# tally-controller-shield.net
KiCad netlist of a schematic drawn in EAGLE
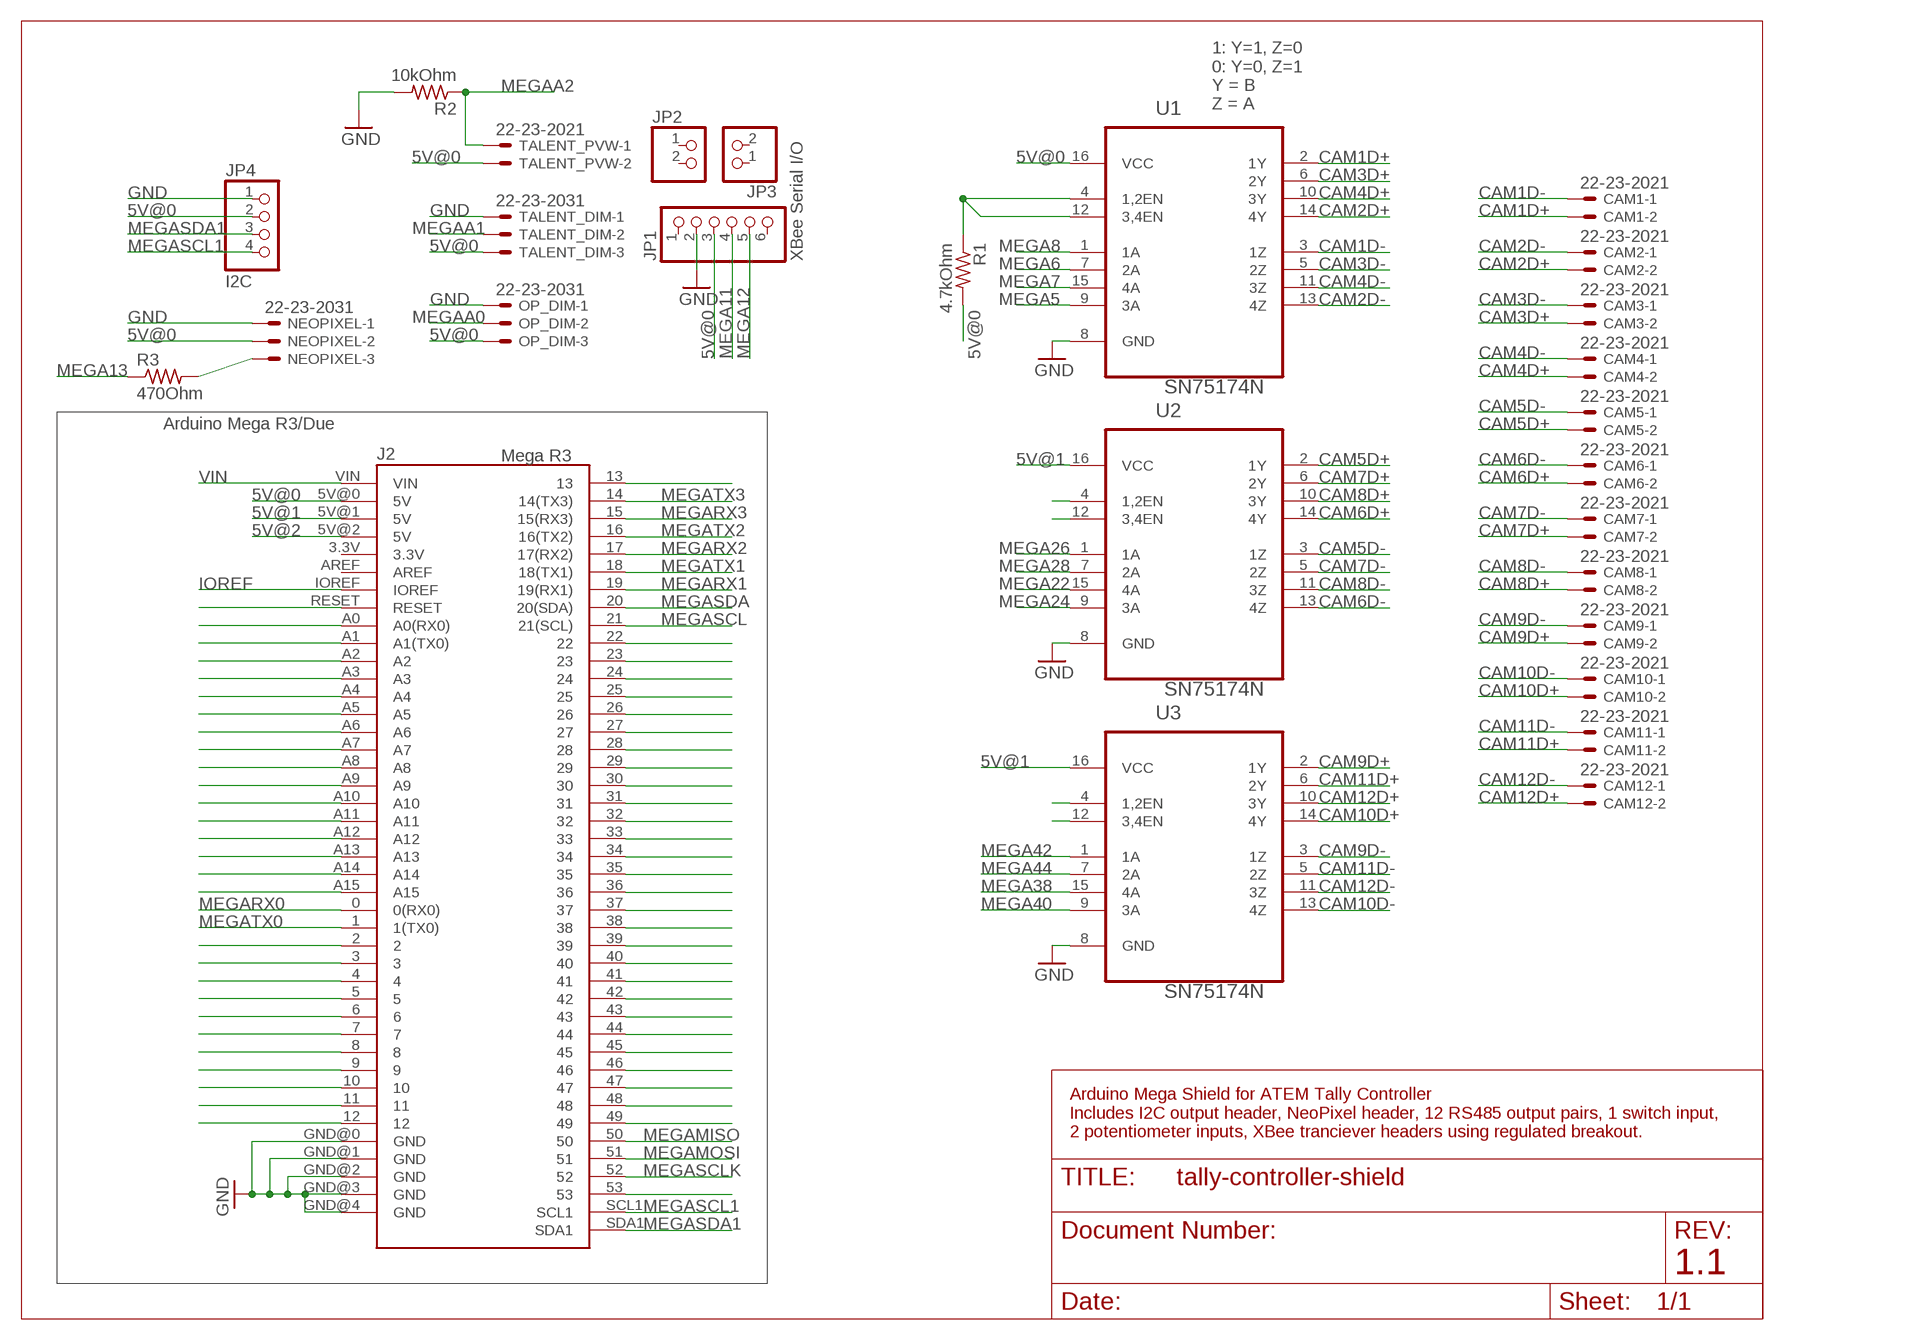
[diagram p0: schematic, sheet 1]

(export (version "E")
  (design (tool "Eeschema 10.0.6"))
  (components
    (comp (ref "CAM1")
      (value "22-23-2021")
      (footprint "eagle-import:22-23-2021")
      (fields (field (name "MF") "MOLEX"))
      (libsource (lib "eagle-import") (part "22-23-2021"))
    )
    (comp (ref "CAM2")
      (value "22-23-2021")
      (footprint "eagle-import:22-23-2021")
      (fields (field (name "MF") "MOLEX"))
      (libsource (lib "eagle-import") (part "22-23-2021"))
    )
    (comp (ref "CAM3")
      (value "22-23-2021")
      (footprint "eagle-import:22-23-2021")
      (fields (field (name "MF") "MOLEX"))
      (libsource (lib "eagle-import") (part "22-23-2021"))
    )
    (comp (ref "CAM4")
      (value "22-23-2021")
      (footprint "eagle-import:22-23-2021")
      (fields (field (name "MF") "MOLEX"))
      (libsource (lib "eagle-import") (part "22-23-2021"))
    )
    (comp (ref "CAM5")
      (value "22-23-2021")
      (footprint "eagle-import:22-23-2021")
      (fields (field (name "MF") "MOLEX"))
      (libsource (lib "eagle-import") (part "22-23-2021"))
    )
    (comp (ref "CAM6")
      (value "22-23-2021")
      (footprint "eagle-import:22-23-2021")
      (fields (field (name "MF") "MOLEX"))
      (libsource (lib "eagle-import") (part "22-23-2021"))
    )
    (comp (ref "CAM7")
      (value "22-23-2021")
      (footprint "eagle-import:22-23-2021")
      (fields (field (name "MF") "MOLEX"))
      (libsource (lib "eagle-import") (part "22-23-2021"))
    )
    (comp (ref "CAM8")
      (value "22-23-2021")
      (footprint "eagle-import:22-23-2021")
      (fields (field (name "MF") "MOLEX"))
      (libsource (lib "eagle-import") (part "22-23-2021"))
    )
    (comp (ref "CAM9")
      (value "22-23-2021")
      (footprint "eagle-import:22-23-2021")
      (fields (field (name "MF") "MOLEX"))
      (libsource (lib "eagle-import") (part "22-23-2021"))
    )
    (comp (ref "CAM10")
      (value "22-23-2021")
      (footprint "eagle-import:22-23-2021")
      (fields (field (name "MF") "MOLEX"))
      (libsource (lib "eagle-import") (part "22-23-2021"))
    )
    (comp (ref "CAM11")
      (value "22-23-2021")
      (footprint "eagle-import:22-23-2021")
      (fields (field (name "MF") "MOLEX"))
      (libsource (lib "eagle-import") (part "22-23-2021"))
    )
    (comp (ref "CAM12")
      (value "22-23-2021")
      (footprint "eagle-import:22-23-2021")
      (fields (field (name "MF") "MOLEX"))
      (libsource (lib "eagle-import") (part "22-23-2021"))
    )
    (comp (ref "J2")
      (value "Mega R3")
      (footprint "eagle-import:ARDUINO_MEGA")
      (libsource (lib "eagle-import") (part "ARDUINO-MEGAFULL"))
    )
    (comp (ref "JP1")
      (value "XBee Serial I/O")
      (footprint "eagle-import:1X06")
      (libsource (lib "eagle-import") (part "PINHD-1X6"))
    )
    (comp (ref "JP2")
      (value "PINHD-1X2")
      (footprint "eagle-import:1X02")
      (libsource (lib "eagle-import") (part "PINHD-1X2"))
    )
    (comp (ref "JP3")
      (value "PINHD-1X2")
      (footprint "eagle-import:1X02")
      (libsource (lib "eagle-import") (part "PINHD-1X2"))
    )
    (comp (ref "JP4")
      (value "I2C")
      (footprint "eagle-import:1X04")
      (libsource (lib "eagle-import") (part "PINHD-1X4"))
    )
    (comp (ref "NEOPIXEL")
      (value "22-23-2031")
      (footprint "eagle-import:22-23-2031")
      (fields (field (name "MF") "MOLEX"))
      (libsource (lib "eagle-import") (part "22-23-2031"))
    )
    (comp (ref "OP_DIM")
      (value "22-23-2031")
      (footprint "eagle-import:22-23-2031")
      (fields (field (name "MF") "MOLEX"))
      (libsource (lib "eagle-import") (part "22-23-2031"))
    )
    (comp (ref "R1")
      (value "4.7kOhm")
      (footprint "eagle-import:0207_10")
      (libsource (lib "eagle-import") (part "R-US_0207/10"))
    )
    (comp (ref "R2")
      (value "10kOhm")
      (footprint "eagle-import:0207_10")
      (libsource (lib "eagle-import") (part "R-US_0207/10"))
    )
    (comp (ref "R3")
      (value "470Ohm")
      (footprint "eagle-import:0207_10")
      (libsource (lib "eagle-import") (part "R-US_0207/10"))
    )
    (comp (ref "TALENT_DIM")
      (value "22-23-2031")
      (footprint "eagle-import:22-23-2031")
      (fields (field (name "MF") "MOLEX"))
      (libsource (lib "eagle-import") (part "22-23-2031"))
    )
    (comp (ref "TALENT_PVW")
      (value "22-23-2021")
      (footprint "eagle-import:22-23-2021")
      (fields (field (name "MF") "MOLEX"))
      (libsource (lib "eagle-import") (part "22-23-2021"))
    )
    (comp (ref "U1")
      (value "SN75174N")
      (footprint "eagle-import:DIP254P762X508-16")
      (fields (field (name "MF") "Texas Instruments"))
      (libsource (lib "eagle-import") (part "SN75174N"))
    )
    (comp (ref "U2")
      (value "SN75174N")
      (footprint "eagle-import:DIP254P762X508-16")
      (fields (field (name "MF") "Texas Instruments"))
      (libsource (lib "eagle-import") (part "SN75174N"))
    )
    (comp (ref "U3")
      (value "SN75174N")
      (footprint "eagle-import:DIP254P762X508-16")
      (fields (field (name "MF") "Texas Instruments"))
      (libsource (lib "eagle-import") (part "SN75174N"))
    )
  )
  (nets
    (net (code "1") (name "/5V@0") (class "Default")
      (node (ref "J2") (pin "5V@0") (pinfunction "5V_5V@0") (pintype "bidirectional"))
      (node (ref "JP1") (pin "3") (pinfunction "3_3") (pintype "passive"))
      (node (ref "JP4") (pin "2") (pinfunction "2_2") (pintype "passive"))
      (node (ref "NEOPIXEL") (pin "2") (pinfunction "S_2") (pintype "passive"))
      (node (ref "OP_DIM") (pin "3") (pinfunction "S_3") (pintype "passive"))
      (node (ref "R1") (pin "2") (pinfunction "2_2") (pintype "passive"))
      (node (ref "TALENT_DIM") (pin "3") (pinfunction "S_3") (pintype "passive"))
      (node (ref "TALENT_PVW") (pin "2") (pinfunction "S_2") (pintype "passive"))
      (node (ref "U1") (pin "16") (pinfunction "VCC_16") (pintype "power_in"))
    )
    (net (code "2") (name "/5V@1") (class "Default")
      (node (ref "J2") (pin "5V@1") (pinfunction "5V_5V@1") (pintype "bidirectional"))
      (node (ref "U2") (pin "16") (pinfunction "VCC_16") (pintype "power_in"))
      (node (ref "U3") (pin "16") (pinfunction "VCC_16") (pintype "power_in"))
    )
    (net (code "3") (name "/5V@2") (class "Default")
      (node (ref "J2") (pin "5V@2") (pinfunction "5V_5V@2") (pintype "bidirectional"))
    )
    (net (code "4") (name "/CAM1D+") (class "Default")
      (node (ref "CAM1") (pin "2") (pinfunction "S_2") (pintype "passive"))
      (node (ref "U1") (pin "2") (pinfunction "1Y_2") (pintype "output"))
    )
    (net (code "5") (name "/CAM1D-") (class "Default")
      (node (ref "CAM1") (pin "1") (pinfunction "S_1") (pintype "passive"))
      (node (ref "U1") (pin "3") (pinfunction "1Z_3") (pintype "output"))
    )
    (net (code "6") (name "/CAM2D+") (class "Default")
      (node (ref "CAM2") (pin "2") (pinfunction "S_2") (pintype "passive"))
      (node (ref "U1") (pin "14") (pinfunction "4Y_14") (pintype "output"))
    )
    (net (code "7") (name "/CAM2D-") (class "Default")
      (node (ref "CAM2") (pin "1") (pinfunction "S_1") (pintype "passive"))
      (node (ref "U1") (pin "13") (pinfunction "4Z_13") (pintype "output"))
    )
    (net (code "8") (name "/CAM3D+") (class "Default")
      (node (ref "CAM3") (pin "2") (pinfunction "S_2") (pintype "passive"))
      (node (ref "U1") (pin "6") (pinfunction "2Y_6") (pintype "output"))
    )
    (net (code "9") (name "/CAM3D-") (class "Default")
      (node (ref "CAM3") (pin "1") (pinfunction "S_1") (pintype "passive"))
      (node (ref "U1") (pin "5") (pinfunction "2Z_5") (pintype "output"))
    )
    (net (code "10") (name "/CAM4D+") (class "Default")
      (node (ref "CAM4") (pin "2") (pinfunction "S_2") (pintype "passive"))
      (node (ref "U1") (pin "10") (pinfunction "3Y_10") (pintype "output"))
    )
    (net (code "11") (name "/CAM4D-") (class "Default")
      (node (ref "CAM4") (pin "1") (pinfunction "S_1") (pintype "passive"))
      (node (ref "U1") (pin "11") (pinfunction "3Z_11") (pintype "output"))
    )
    (net (code "12") (name "/CAM5D+") (class "Default")
      (node (ref "CAM5") (pin "2") (pinfunction "S_2") (pintype "passive"))
      (node (ref "U2") (pin "2") (pinfunction "1Y_2") (pintype "output"))
    )
    (net (code "13") (name "/CAM5D-") (class "Default")
      (node (ref "CAM5") (pin "1") (pinfunction "S_1") (pintype "passive"))
      (node (ref "U2") (pin "3") (pinfunction "1Z_3") (pintype "output"))
    )
    (net (code "14") (name "/CAM6D+") (class "Default")
      (node (ref "CAM6") (pin "2") (pinfunction "S_2") (pintype "passive"))
      (node (ref "U2") (pin "14") (pinfunction "4Y_14") (pintype "output"))
    )
    (net (code "15") (name "/CAM6D-") (class "Default")
      (node (ref "CAM6") (pin "1") (pinfunction "S_1") (pintype "passive"))
      (node (ref "U2") (pin "13") (pinfunction "4Z_13") (pintype "output"))
    )
    (net (code "16") (name "/CAM7D+") (class "Default")
      (node (ref "CAM7") (pin "2") (pinfunction "S_2") (pintype "passive"))
      (node (ref "U2") (pin "6") (pinfunction "2Y_6") (pintype "output"))
    )
    (net (code "17") (name "/CAM7D-") (class "Default")
      (node (ref "CAM7") (pin "1") (pinfunction "S_1") (pintype "passive"))
      (node (ref "U2") (pin "5") (pinfunction "2Z_5") (pintype "output"))
    )
    (net (code "18") (name "/CAM8D+") (class "Default")
      (node (ref "CAM8") (pin "2") (pinfunction "S_2") (pintype "passive"))
      (node (ref "U2") (pin "10") (pinfunction "3Y_10") (pintype "output"))
    )
    (net (code "19") (name "/CAM8D-") (class "Default")
      (node (ref "CAM8") (pin "1") (pinfunction "S_1") (pintype "passive"))
      (node (ref "U2") (pin "11") (pinfunction "3Z_11") (pintype "output"))
    )
    (net (code "20") (name "/CAM9D+") (class "Default")
      (node (ref "CAM9") (pin "2") (pinfunction "S_2") (pintype "passive"))
      (node (ref "U3") (pin "2") (pinfunction "1Y_2") (pintype "output"))
    )
    (net (code "21") (name "/CAM9D-") (class "Default")
      (node (ref "CAM9") (pin "1") (pinfunction "S_1") (pintype "passive"))
      (node (ref "U3") (pin "3") (pinfunction "1Z_3") (pintype "output"))
    )
    (net (code "22") (name "/CAM10D+") (class "Default")
      (node (ref "CAM10") (pin "2") (pinfunction "S_2") (pintype "passive"))
      (node (ref "U3") (pin "14") (pinfunction "4Y_14") (pintype "output"))
    )
    (net (code "23") (name "/CAM10D-") (class "Default")
      (node (ref "CAM10") (pin "1") (pinfunction "S_1") (pintype "passive"))
      (node (ref "U3") (pin "13") (pinfunction "4Z_13") (pintype "output"))
    )
    (net (code "24") (name "/CAM11D+") (class "Default")
      (node (ref "CAM11") (pin "2") (pinfunction "S_2") (pintype "passive"))
      (node (ref "U3") (pin "6") (pinfunction "2Y_6") (pintype "output"))
    )
    (net (code "25") (name "/CAM11D-") (class "Default")
      (node (ref "CAM11") (pin "1") (pinfunction "S_1") (pintype "passive"))
      (node (ref "U3") (pin "5") (pinfunction "2Z_5") (pintype "output"))
    )
    (net (code "26") (name "/CAM12D+") (class "Default")
      (node (ref "CAM12") (pin "2") (pinfunction "S_2") (pintype "passive"))
      (node (ref "U3") (pin "10") (pinfunction "3Y_10") (pintype "output"))
    )
    (net (code "27") (name "/CAM12D-") (class "Default")
      (node (ref "CAM12") (pin "1") (pinfunction "S_1") (pintype "passive"))
      (node (ref "U3") (pin "11") (pinfunction "3Z_11") (pintype "output"))
    )
    (net (code "28") (name "/IOREF") (class "Default")
      (node (ref "J2") (pin "IOREF") (pinfunction "IOREF_IOREF") (pintype "bidirectional"))
    )
    (net (code "29") (name "/MEGA5") (class "Default")
      (node (ref "J2") (pin "5") (pinfunction "5_5") (pintype "bidirectional"))
      (node (ref "U1") (pin "9") (pinfunction "3A_9") (pintype "input"))
    )
    (net (code "30") (name "/MEGA6") (class "Default")
      (node (ref "J2") (pin "6") (pinfunction "6_6") (pintype "bidirectional"))
      (node (ref "U1") (pin "7") (pinfunction "2A_7") (pintype "input"))
    )
    (net (code "31") (name "/MEGA7") (class "Default")
      (node (ref "J2") (pin "7") (pinfunction "7_7") (pintype "bidirectional"))
      (node (ref "U1") (pin "15") (pinfunction "4A_15") (pintype "input"))
    )
    (net (code "32") (name "/MEGA8") (class "Default")
      (node (ref "J2") (pin "8") (pinfunction "8_8") (pintype "bidirectional"))
      (node (ref "U1") (pin "1") (pinfunction "1A_1") (pintype "input"))
    )
    (net (code "33") (name "/MEGA11") (class "Default")
      (node (ref "J2") (pin "11") (pinfunction "11_11") (pintype "bidirectional"))
      (node (ref "JP1") (pin "4") (pinfunction "4_4") (pintype "passive"))
    )
    (net (code "34") (name "/MEGA12") (class "Default")
      (node (ref "J2") (pin "12") (pinfunction "12_12") (pintype "bidirectional"))
      (node (ref "JP1") (pin "5") (pinfunction "5_5") (pintype "passive"))
    )
    (net (code "35") (name "/MEGA13") (class "Default")
      (node (ref "J2") (pin "13") (pinfunction "13_13") (pintype "bidirectional"))
      (node (ref "R3") (pin "1") (pinfunction "1_1") (pintype "passive"))
    )
    (net (code "36") (name "/MEGA22") (class "Default")
      (node (ref "J2") (pin "22") (pinfunction "22_22") (pintype "bidirectional"))
      (node (ref "U2") (pin "15") (pinfunction "4A_15") (pintype "input"))
    )
    (net (code "37") (name "/MEGA24") (class "Default")
      (node (ref "J2") (pin "24") (pinfunction "24_24") (pintype "bidirectional"))
      (node (ref "U2") (pin "9") (pinfunction "3A_9") (pintype "input"))
    )
    (net (code "38") (name "/MEGA26") (class "Default")
      (node (ref "J2") (pin "26") (pinfunction "26_26") (pintype "bidirectional"))
      (node (ref "U2") (pin "1") (pinfunction "1A_1") (pintype "input"))
    )
    (net (code "39") (name "/MEGA28") (class "Default")
      (node (ref "J2") (pin "28") (pinfunction "28_28") (pintype "bidirectional"))
      (node (ref "U2") (pin "7") (pinfunction "2A_7") (pintype "input"))
    )
    (net (code "40") (name "/MEGA38") (class "Default")
      (node (ref "J2") (pin "38") (pinfunction "38_38") (pintype "bidirectional"))
      (node (ref "U3") (pin "15") (pinfunction "4A_15") (pintype "input"))
    )
    (net (code "41") (name "/MEGA40") (class "Default")
      (node (ref "J2") (pin "40") (pinfunction "40_40") (pintype "bidirectional"))
      (node (ref "U3") (pin "9") (pinfunction "3A_9") (pintype "input"))
    )
    (net (code "42") (name "/MEGA42") (class "Default")
      (node (ref "J2") (pin "42") (pinfunction "42_42") (pintype "bidirectional"))
      (node (ref "U3") (pin "1") (pinfunction "1A_1") (pintype "input"))
    )
    (net (code "43") (name "/MEGA44") (class "Default")
      (node (ref "J2") (pin "44") (pinfunction "44_44") (pintype "bidirectional"))
      (node (ref "U3") (pin "7") (pinfunction "2A_7") (pintype "input"))
    )
    (net (code "44") (name "/MEGAA0") (class "Default")
      (node (ref "J2") (pin "A0") (pinfunction "A0(RX0)_A0") (pintype "bidirectional"))
      (node (ref "OP_DIM") (pin "2") (pinfunction "S_2") (pintype "passive"))
    )
    (net (code "45") (name "/MEGAA1") (class "Default")
      (node (ref "J2") (pin "A1") (pinfunction "A1(TX0)_A1") (pintype "bidirectional"))
      (node (ref "TALENT_DIM") (pin "2") (pinfunction "S_2") (pintype "passive"))
    )
    (net (code "46") (name "/MEGAA2") (class "Default")
      (node (ref "J2") (pin "A2") (pinfunction "A2_A2") (pintype "bidirectional"))
      (node (ref "R2") (pin "1") (pinfunction "1_1") (pintype "passive"))
      (node (ref "TALENT_PVW") (pin "1") (pinfunction "S_1") (pintype "passive"))
    )
    (net (code "47") (name "/MEGAMISO") (class "Default")
      (node (ref "J2") (pin "50") (pinfunction "50_50") (pintype "bidirectional"))
    )
    (net (code "48") (name "/MEGAMOSI") (class "Default")
      (node (ref "J2") (pin "51") (pinfunction "51_51") (pintype "bidirectional"))
    )
    (net (code "49") (name "/MEGARX0") (class "Default")
      (node (ref "J2") (pin "0") (pinfunction "0(RX0)_0") (pintype "bidirectional"))
    )
    (net (code "50") (name "/MEGARX1") (class "Default")
      (node (ref "J2") (pin "19") (pinfunction "19(RX1)_19") (pintype "bidirectional"))
    )
    (net (code "51") (name "/MEGARX2") (class "Default")
      (node (ref "J2") (pin "17") (pinfunction "17(RX2)_17") (pintype "bidirectional"))
    )
    (net (code "52") (name "/MEGARX3") (class "Default")
      (node (ref "J2") (pin "15") (pinfunction "15(RX3)_15") (pintype "bidirectional"))
    )
    (net (code "53") (name "/MEGASCL") (class "Default")
      (node (ref "J2") (pin "21") (pinfunction "21(SCL)_21") (pintype "bidirectional"))
    )
    (net (code "54") (name "/MEGASCL1") (class "Default")
      (node (ref "J2") (pin "SCL1") (pinfunction "SCL1_SCL1") (pintype "bidirectional"))
      (node (ref "JP4") (pin "4") (pinfunction "4_4") (pintype "passive"))
    )
    (net (code "55") (name "/MEGASCLK") (class "Default")
      (node (ref "J2") (pin "52") (pinfunction "52_52") (pintype "bidirectional"))
    )
    (net (code "56") (name "/MEGASDA") (class "Default")
      (node (ref "J2") (pin "20") (pinfunction "20(SDA)_20") (pintype "bidirectional"))
    )
    (net (code "57") (name "/MEGASDA1") (class "Default")
      (node (ref "J2") (pin "SDA1") (pinfunction "SDA1_SDA1") (pintype "bidirectional"))
      (node (ref "JP4") (pin "3") (pinfunction "3_3") (pintype "passive"))
    )
    (net (code "58") (name "/MEGATX0") (class "Default")
      (node (ref "J2") (pin "1") (pinfunction "1(TX0)_1") (pintype "bidirectional"))
    )
    (net (code "59") (name "/MEGATX1") (class "Default")
      (node (ref "J2") (pin "18") (pinfunction "18(TX1)_18") (pintype "bidirectional"))
    )
    (net (code "60") (name "/MEGATX2") (class "Default")
      (node (ref "J2") (pin "16") (pinfunction "16(TX2)_16") (pintype "bidirectional"))
    )
    (net (code "61") (name "/MEGATX3") (class "Default")
      (node (ref "J2") (pin "14") (pinfunction "14(TX3)_14") (pintype "bidirectional"))
    )
    (net (code "62") (name "/RS485EN") (class "Default")
      (node (ref "R1") (pin "1") (pinfunction "1_1") (pintype "passive"))
      (node (ref "U1") (pin "12") (pinfunction "3,4EN_12") (pintype "input"))
      (node (ref "U1") (pin "4") (pinfunction "1,2EN_4") (pintype "input"))
      (node (ref "U2") (pin "12") (pinfunction "3,4EN_12") (pintype "input"))
      (node (ref "U2") (pin "4") (pinfunction "1,2EN_4") (pintype "input"))
      (node (ref "U3") (pin "12") (pinfunction "3,4EN_12") (pintype "input"))
      (node (ref "U3") (pin "4") (pinfunction "1,2EN_4") (pintype "input"))
    )
    (net (code "63") (name "/VIN") (class "Default")
      (node (ref "J2") (pin "VIN") (pinfunction "VIN_VIN") (pintype "bidirectional"))
    )
    (net (code "64") (name "GND") (class "Default")
      (node (ref "J2") (pin "GND@0") (pinfunction "GND_GND@0") (pintype "bidirectional"))
      (node (ref "J2") (pin "GND@1") (pinfunction "GND_GND@1") (pintype "bidirectional"))
      (node (ref "J2") (pin "GND@2") (pinfunction "GND_GND@2") (pintype "bidirectional"))
      (node (ref "J2") (pin "GND@3") (pinfunction "GND_GND@3") (pintype "bidirectional"))
      (node (ref "J2") (pin "GND@4") (pinfunction "GND_GND@4") (pintype "bidirectional"))
      (node (ref "JP1") (pin "2") (pinfunction "2_2") (pintype "passive"))
      (node (ref "JP4") (pin "1") (pinfunction "1_1") (pintype "passive"))
      (node (ref "NEOPIXEL") (pin "1") (pinfunction "S_1") (pintype "passive"))
      (node (ref "OP_DIM") (pin "1") (pinfunction "S_1") (pintype "passive"))
      (node (ref "R2") (pin "2") (pinfunction "2_2") (pintype "passive"))
      (node (ref "TALENT_DIM") (pin "1") (pinfunction "S_1") (pintype "passive"))
      (node (ref "U1") (pin "8") (pinfunction "GND_8") (pintype "passive"))
      (node (ref "U2") (pin "8") (pinfunction "GND_8") (pintype "passive"))
      (node (ref "U3") (pin "8") (pinfunction "GND_8") (pintype "passive"))
    )
    (net (code "65") (name "Net-(NEOPIXELC-S)") (class "Default")
      (node (ref "NEOPIXEL") (pin "3") (pinfunction "S_3") (pintype "passive"))
      (node (ref "R3") (pin "2") (pinfunction "2_2") (pintype "passive"))
    )
    (net (code "66") (name "unconnected-(J2-Pad2)") (class "Default")
      (node (ref "J2") (pin "2") (pinfunction "2_2") (pintype "bidirectional"))
    )
    (net (code "67") (name "unconnected-(J2-Pad3)") (class "Default")
      (node (ref "J2") (pin "3") (pinfunction "3_3") (pintype "bidirectional"))
    )
    (net (code "68") (name "unconnected-(J2-Pad3.3V)") (class "Default")
      (node (ref "J2") (pin "3.3V") (pinfunction "3.3V_3.3V") (pintype "bidirectional"))
    )
    (net (code "69") (name "unconnected-(J2-Pad4)") (class "Default")
      (node (ref "J2") (pin "4") (pinfunction "4_4") (pintype "bidirectional"))
    )
    (net (code "70") (name "unconnected-(J2-Pad9)") (class "Default")
      (node (ref "J2") (pin "9") (pinfunction "9_9") (pintype "bidirectional"))
    )
    (net (code "71") (name "unconnected-(J2-Pad10)") (class "Default")
      (node (ref "J2") (pin "10") (pinfunction "10_10") (pintype "bidirectional"))
    )
    (net (code "72") (name "unconnected-(J2-Pad23)") (class "Default")
      (node (ref "J2") (pin "23") (pinfunction "23_23") (pintype "bidirectional"))
    )
    (net (code "73") (name "unconnected-(J2-Pad25)") (class "Default")
      (node (ref "J2") (pin "25") (pinfunction "25_25") (pintype "bidirectional"))
    )
    (net (code "74") (name "unconnected-(J2-Pad27)") (class "Default")
      (node (ref "J2") (pin "27") (pinfunction "27_27") (pintype "bidirectional"))
    )
    (net (code "75") (name "unconnected-(J2-Pad29)") (class "Default")
      (node (ref "J2") (pin "29") (pinfunction "29_29") (pintype "bidirectional"))
    )
    (net (code "76") (name "unconnected-(J2-Pad30)") (class "Default")
      (node (ref "J2") (pin "30") (pinfunction "30_30") (pintype "bidirectional"))
    )
    (net (code "77") (name "unconnected-(J2-Pad31)") (class "Default")
      (node (ref "J2") (pin "31") (pinfunction "31_31") (pintype "bidirectional"))
    )
    (net (code "78") (name "unconnected-(J2-Pad32)") (class "Default")
      (node (ref "J2") (pin "32") (pinfunction "32_32") (pintype "bidirectional"))
    )
    (net (code "79") (name "unconnected-(J2-Pad33)") (class "Default")
      (node (ref "J2") (pin "33") (pinfunction "33_33") (pintype "bidirectional"))
    )
    (net (code "80") (name "unconnected-(J2-Pad34)") (class "Default")
      (node (ref "J2") (pin "34") (pinfunction "34_34") (pintype "bidirectional"))
    )
    (net (code "81") (name "unconnected-(J2-Pad35)") (class "Default")
      (node (ref "J2") (pin "35") (pinfunction "35_35") (pintype "bidirectional"))
    )
    (net (code "82") (name "unconnected-(J2-Pad36)") (class "Default")
      (node (ref "J2") (pin "36") (pinfunction "36_36") (pintype "bidirectional"))
    )
    (net (code "83") (name "unconnected-(J2-Pad37)") (class "Default")
      (node (ref "J2") (pin "37") (pinfunction "37_37") (pintype "bidirectional"))
    )
    (net (code "84") (name "unconnected-(J2-Pad39)") (class "Default")
      (node (ref "J2") (pin "39") (pinfunction "39_39") (pintype "bidirectional"))
    )
    (net (code "85") (name "unconnected-(J2-Pad41)") (class "Default")
      (node (ref "J2") (pin "41") (pinfunction "41_41") (pintype "bidirectional"))
    )
    (net (code "86") (name "unconnected-(J2-Pad43)") (class "Default")
      (node (ref "J2") (pin "43") (pinfunction "43_43") (pintype "bidirectional"))
    )
    (net (code "87") (name "unconnected-(J2-Pad45)") (class "Default")
      (node (ref "J2") (pin "45") (pinfunction "45_45") (pintype "bidirectional"))
    )
    (net (code "88") (name "unconnected-(J2-Pad46)") (class "Default")
      (node (ref "J2") (pin "46") (pinfunction "46_46") (pintype "bidirectional"))
    )
    (net (code "89") (name "unconnected-(J2-Pad47)") (class "Default")
      (node (ref "J2") (pin "47") (pinfunction "47_47") (pintype "bidirectional"))
    )
    (net (code "90") (name "unconnected-(J2-Pad48)") (class "Default")
      (node (ref "J2") (pin "48") (pinfunction "48_48") (pintype "bidirectional"))
    )
    (net (code "91") (name "unconnected-(J2-Pad49)") (class "Default")
      (node (ref "J2") (pin "49") (pinfunction "49_49") (pintype "bidirectional"))
    )
    (net (code "92") (name "unconnected-(J2-Pad53)") (class "Default")
      (node (ref "J2") (pin "53") (pinfunction "53_53") (pintype "bidirectional"))
    )
    (net (code "93") (name "unconnected-(J2-PadA3)") (class "Default")
      (node (ref "J2") (pin "A3") (pinfunction "A3_A3") (pintype "bidirectional"))
    )
    (net (code "94") (name "unconnected-(J2-PadA4)") (class "Default")
      (node (ref "J2") (pin "A4") (pinfunction "A4_A4") (pintype "bidirectional"))
    )
    (net (code "95") (name "unconnected-(J2-PadA5)") (class "Default")
      (node (ref "J2") (pin "A5") (pinfunction "A5_A5") (pintype "bidirectional"))
    )
    (net (code "96") (name "unconnected-(J2-PadA6)") (class "Default")
      (node (ref "J2") (pin "A6") (pinfunction "A6_A6") (pintype "bidirectional"))
    )
    (net (code "97") (name "unconnected-(J2-PadA7)") (class "Default")
      (node (ref "J2") (pin "A7") (pinfunction "A7_A7") (pintype "bidirectional"))
    )
    (net (code "98") (name "unconnected-(J2-PadA8)") (class "Default")
      (node (ref "J2") (pin "A8") (pinfunction "A8_A8") (pintype "bidirectional"))
    )
    (net (code "99") (name "unconnected-(J2-PadA9)") (class "Default")
      (node (ref "J2") (pin "A9") (pinfunction "A9_A9") (pintype "bidirectional"))
    )
    (net (code "100") (name "unconnected-(J2-PadA10)") (class "Default")
      (node (ref "J2") (pin "A10") (pinfunction "A10_A10") (pintype "bidirectional"))
    )
    (net (code "101") (name "unconnected-(J2-PadA11)") (class "Default")
      (node (ref "J2") (pin "A11") (pinfunction "A11_A11") (pintype "bidirectional"))
    )
    (net (code "102") (name "unconnected-(J2-PadA12)") (class "Default")
      (node (ref "J2") (pin "A12") (pinfunction "A12_A12") (pintype "bidirectional"))
    )
    (net (code "103") (name "unconnected-(J2-PadA13)") (class "Default")
      (node (ref "J2") (pin "A13") (pinfunction "A13_A13") (pintype "bidirectional"))
    )
    (net (code "104") (name "unconnected-(J2-PadA14)") (class "Default")
      (node (ref "J2") (pin "A14") (pinfunction "A14_A14") (pintype "bidirectional"))
    )
    (net (code "105") (name "unconnected-(J2-PadA15)") (class "Default")
      (node (ref "J2") (pin "A15") (pinfunction "A15_A15") (pintype "bidirectional"))
    )
    (net (code "106") (name "unconnected-(J2-PadAREF)") (class "Default")
      (node (ref "J2") (pin "AREF") (pinfunction "AREF_AREF") (pintype "bidirectional"))
    )
    (net (code "107") (name "unconnected-(J2-PadRESET)") (class "Default")
      (node (ref "J2") (pin "RESET") (pinfunction "RESET_RESET") (pintype "bidirectional"))
    )
    (net (code "108") (name "unconnected-(JP1-Pad1)") (class "Default")
      (node (ref "JP1") (pin "1") (pinfunction "1_1") (pintype "passive"))
    )
    (net (code "109") (name "unconnected-(JP1-Pad6)") (class "Default")
      (node (ref "JP1") (pin "6") (pinfunction "6_6") (pintype "passive"))
    )
    (net (code "110") (name "unconnected-(JP2-Pad1)") (class "Default")
      (node (ref "JP2") (pin "1") (pinfunction "1_1") (pintype "passive"))
    )
    (net (code "111") (name "unconnected-(JP2-Pad2)") (class "Default")
      (node (ref "JP2") (pin "2") (pinfunction "2_2") (pintype "passive"))
    )
    (net (code "112") (name "unconnected-(JP3-Pad1)") (class "Default")
      (node (ref "JP3") (pin "1") (pinfunction "1_1") (pintype "passive"))
    )
    (net (code "113") (name "unconnected-(JP3-Pad2)") (class "Default")
      (node (ref "JP3") (pin "2") (pinfunction "2_2") (pintype "passive"))
    )
  )
)
